# SCH_card0_2025-06-10.net
KiCad netlist of a schematic drawn in EasyEDA
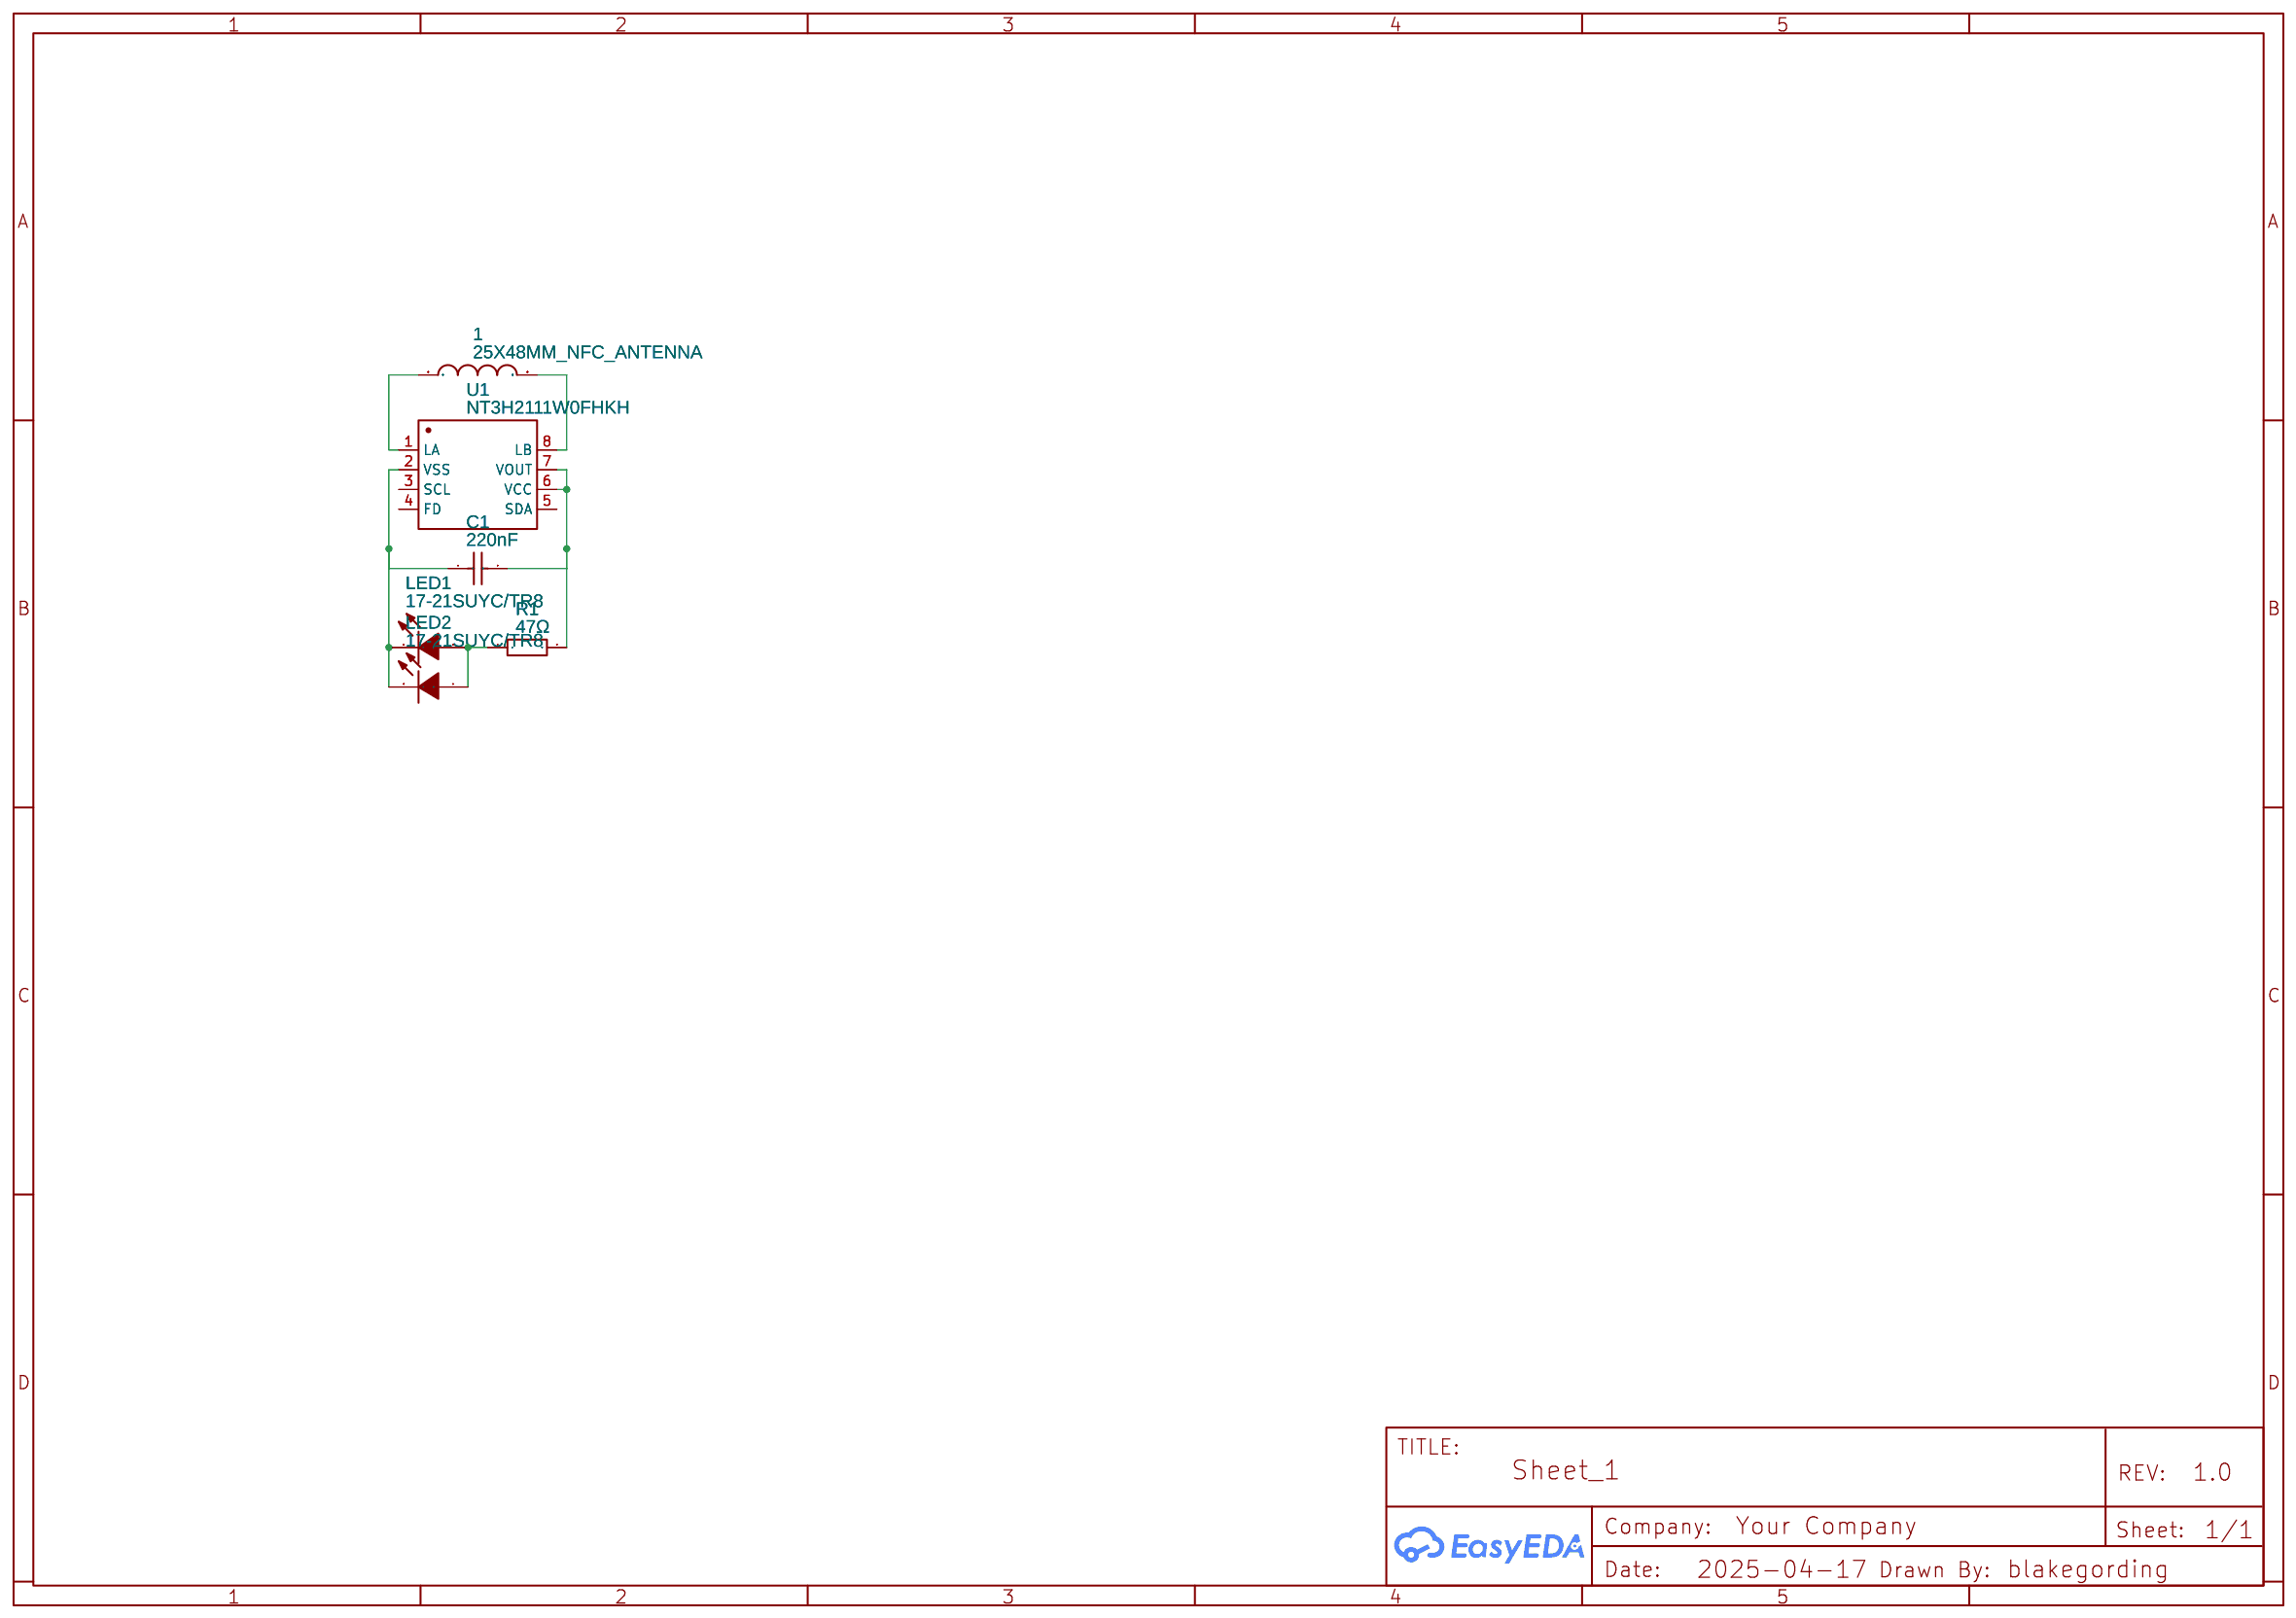
[diagram p0: schematic sheet]

(export (version "E")
  (design (tool "Eeschema 10.0.6"))
  (components
    (comp (ref "1") (value "25X48MM_NFC_ANTENNA") (libsource (lib "") (part "25X48MM_NFC_ANTENNA")))
    (comp (ref "C1")
      (value "220nF")
      (fields
        (field (name "Manufacturer Part") "CL10B224KA8NNNC")
        (field (name "Manufacturer") "SAMSUNG(三星)")
      )
      (libsource (lib "") (part "CL10B224KA8NNNC"))
    )
    (comp (ref "LED1")
      (value "17-21SUYC/TR8")
      (fields (field (name "Manufacturer Part") "KT-0805黄灯") (field (name "Manufacturer") "KENTO"))
      (libsource (lib "") (part "17-21SUYC/TR8"))
    )
    (comp (ref "LED2")
      (value "17-21SUYC/TR8")
      (fields (field (name "Manufacturer Part") "KT-0805黄灯") (field (name "Manufacturer") "KENTO"))
      (libsource (lib "") (part "17-21SUYC/TR8"))
    )
    (comp (ref "R1")
      (value "47Ω")
      (fields
        (field (name "Manufacturer Part") "0603WAF470JT5E")
        (field (name "Manufacturer") "UNI-ROYAL(厚声)")
      )
      (libsource (lib "") (part "0603WAF470JT5E"))
    )
    (comp (ref "U1")
      (value "NT3H2111W0FHKH")
      (fields (field (name "Manufacturer") "NXP(恩智浦)"))
      (libsource (lib "") (part "NT3H2111W0FHKH"))
    )
  )
  (nets
    (net (code "1") (name "Net-(LED1-+)") (class "Default")
      (node (ref "LED1") (pin "1") (pinfunction "+_1") (pintype "unspecified"))
      (node (ref "LED2") (pin "1") (pinfunction "+_1") (pintype "unspecified"))
      (node (ref "R1") (pin "1") (pinfunction "1_1") (pintype "input"))
    )
    (net (code "2") (name "Net-(LED1--)") (class "Default")
      (node (ref "C1") (pin "1") (pinfunction "1_1") (pintype "input"))
      (node (ref "LED1") (pin "2") (pinfunction "-_2") (pintype "unspecified"))
      (node (ref "LED2") (pin "2") (pinfunction "-_2") (pintype "unspecified"))
      (node (ref "U1") (pin "2") (pinfunction "VSS_2") (pintype "unspecified"))
    )
    (net (code "3") (name "Net-(U1-LA)") (class "Default")
      (node (ref "1") (pin "P$1") (pinfunction "P$1_P$1") (pintype "bidirectional"))
      (node (ref "U1") (pin "1") (pinfunction "LA_1") (pintype "unspecified"))
    )
    (net (code "4") (name "Net-(U1-LB)") (class "Default")
      (node (ref "1") (pin "P$2") (pinfunction "P$2_P$2") (pintype "bidirectional"))
      (node (ref "U1") (pin "8") (pinfunction "LB_8") (pintype "unspecified"))
    )
    (net (code "5") (name "Net-(U1-VCC)") (class "Default")
      (node (ref "C1") (pin "2") (pinfunction "2_2") (pintype "input"))
      (node (ref "R1") (pin "2") (pinfunction "2_2") (pintype "input"))
      (node (ref "U1") (pin "6") (pinfunction "VCC_6") (pintype "unspecified"))
      (node (ref "U1") (pin "7") (pinfunction "VOUT_7") (pintype "unspecified"))
    )
    (net (code "6") (name "unconnected-(U1-FD-Pad4)") (class "Default")
      (node (ref "U1") (pin "4") (pinfunction "FD_4") (pintype "unspecified"))
    )
    (net (code "7") (name "unconnected-(U1-SCL-Pad3)") (class "Default")
      (node (ref "U1") (pin "3") (pinfunction "SCL_3") (pintype "unspecified"))
    )
    (net (code "8") (name "unconnected-(U1-SDA-Pad5)") (class "Default")
      (node (ref "U1") (pin "5") (pinfunction "SDA_5") (pintype "unspecified"))
    )
  )
)
